# Converter.net
KiCad netlist of a schematic drawn in Altium Designer
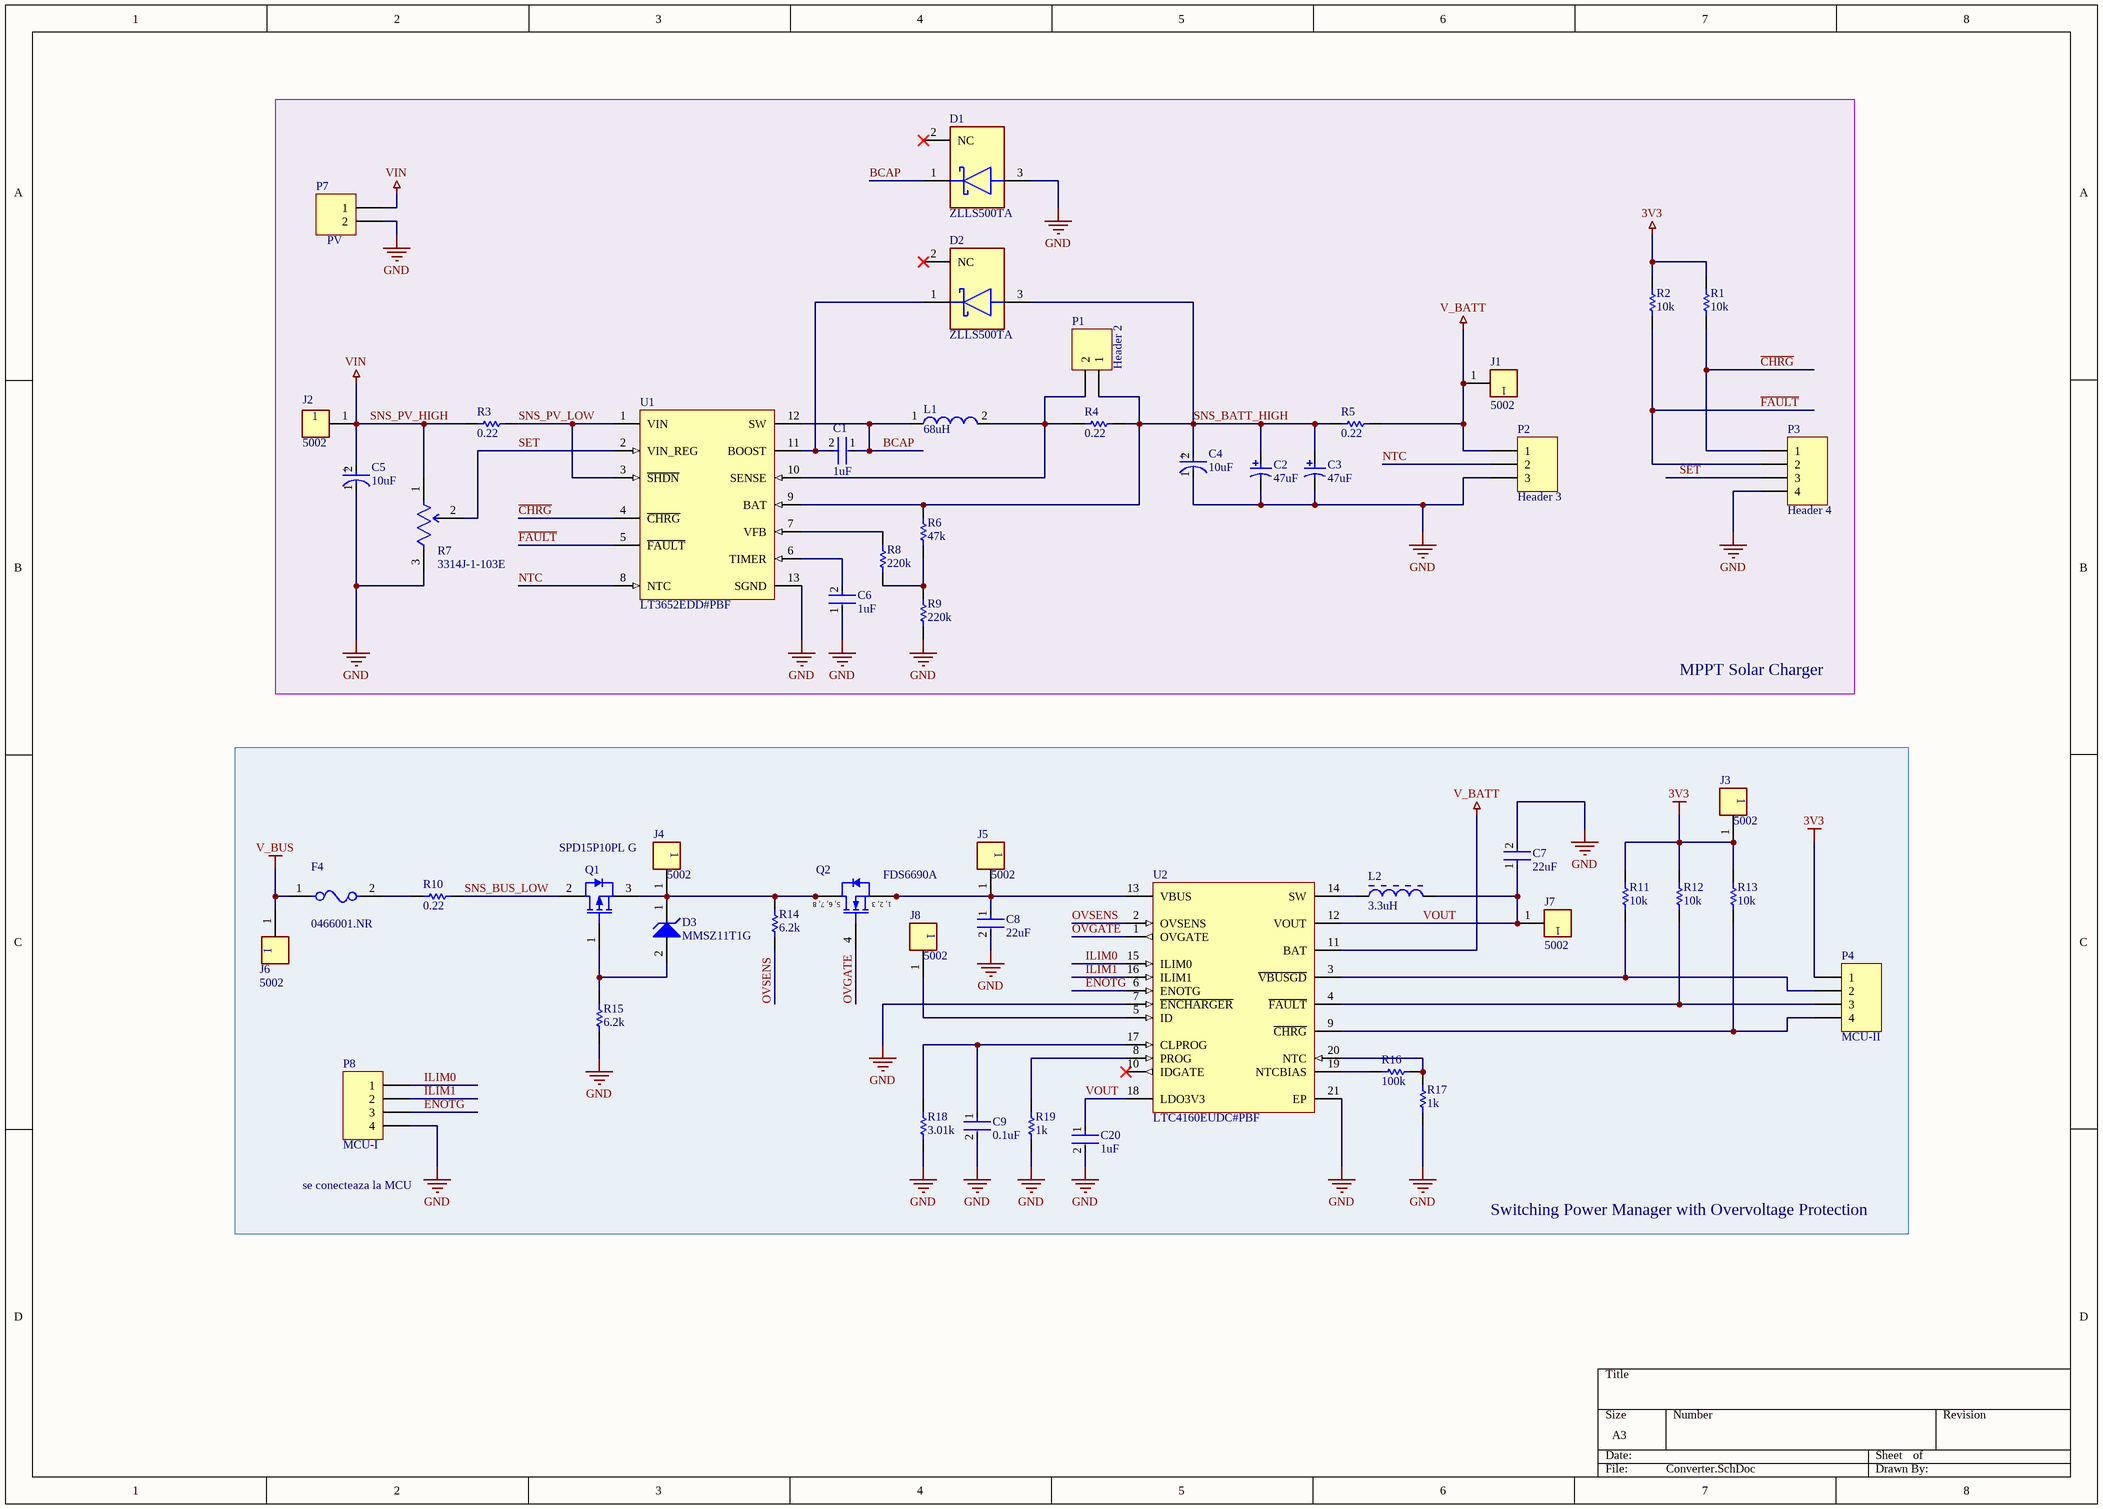
[diagram p0: Converter.SchDoc]

(export (version "E")
  (design (tool "Eeschema 10.0.6"))
  (components
    (comp (ref "C1")
      (value "1uF")
      (footprint "FP-C1608-080-0_1-IPC_B")
      (description "Multilayer Ceramic Capacitors 1μF ±10% 16V X7R SMD 0603")
      (fields (field (name "VOLTAGE") "16V") (field (name "TOLERANCE") "10%"))
      (libsource (lib "Altium Content Vault") (part "236180d848d6139a670b325ea6854c9"))
    )
    (comp (ref "C2")
      (value "47uF")
      (footprint "KEMT-T491-D_L")
      (fields (field (name "TOLERANCE") "10%"))
      (libsource (lib "Altium Content Vault") (part "CAP-P-2"))
    )
    (comp (ref "C3")
      (value "47uF")
      (footprint "KEMT-T491-D_L")
      (fields (field (name "TOLERANCE") "10%"))
      (libsource (lib "Altium Content Vault") (part "CAP-P-2"))
    )
    (comp (ref "C4")
      (value "10uF")
      (footprint "FP-T491C106K016AT-MFG")
      (description "CAP TANT 10UF 10% 16V 2312")
      (fields (field (name "VOLTAGE") "16V") (field (name "TOLERANCE") "10%"))
      (libsource (lib "Altium Content Vault") (part "a00bbbee19879c290e62620ae7e47b1"))
    )
    (comp (ref "C5")
      (value "10uF")
      (footprint "FP-T491D-MFG")
      (description "CAP TANT 10UF 10% 25V 2917")
      (fields (field (name "VOLTAGE") "25V") (field (name "TOLERANCE") "20%"))
      (libsource (lib "Altium Content Vault") (part "cf48714ba7e38822c1575c7ec0b6d1f"))
    )
    (comp (ref "C6")
      (value "1uF")
      (footprint "FP-C1608-080-0_1-IPC_B")
      (description "Multilayer Ceramic Capacitors 1μF ±10% 16V X7R SMD 0603")
      (fields (field (name "VOLTAGE") "16V") (field (name "TOLERANCE") "10%"))
      (libsource (lib "Altium Content Vault") (part "236180d848d6139a670b325ea6854c9"))
    )
    (comp (ref "C7")
      (value "22uF")
      (footprint "FP-C2012-125-0_2-IPC_C")
      (description "Multilayer Ceramic Capacitors 22μF ±10% 16V X5R SMD 0805")
      (fields (field (name "TOLERANCE") "10%") (field (name "VOLTAGE") "16V"))
      (libsource (lib "Altium Content Vault") (part "b4654b650e69147ec39a6b967a45e02"))
    )
    (comp (ref "C8")
      (value "22uF")
      (footprint "FP-C2012-125-0_2-IPC_C")
      (description "Multilayer Ceramic Capacitors 22μF ±10% 16V X5R SMD 0805")
      (fields (field (name "TOLERANCE") "10%") (field (name "VOLTAGE") "16V"))
      (libsource (lib "Altium Content Vault") (part "b4654b650e69147ec39a6b967a45e02"))
    )
    (comp (ref "C9")
      (value "0.1uF")
      (footprint "FP-GRM155-0_05-MFG")
      (description "CAP CER 0.1UF 16V X7R 0402")
      (fields (field (name "TOLERANCE") "5%") (field (name "VOLTAGE") "16V"))
      (libsource (lib "Altium Content Vault") (part "02cd4be3c70576c341d710602a673aa"))
    )
    (comp (ref "C20")
      (value "1uF")
      (footprint "FP-0603-L_1_6_0_15-W_0_81-IPC_A")
      (description "General Purpose Ceramic Capacitor, 0603, 1uF, 10%, X5R, 15%, 10V")
      (fields (field (name "TOLERANCE") "10%") (field (name "VOLTAGE") "10V"))
      (libsource (lib "Altium Content Vault") (part "02cd4be3c70576c341d710602a673aa"))
    )
    (comp (ref "D1")
      (value "ZLLS500TA")
      (footprint "FP-SOT23-IPC_B")
      (description "DIODE SCHOTTKY 40V 700MA SOT23-3")
      (libsource (lib "Altium Content Vault") (part "b02bf5cfd78647b0d44792585de17e4"))
    )
    (comp (ref "D2")
      (value "ZLLS500TA")
      (footprint "FP-SOT23-IPC_B")
      (description "DIODE SCHOTTKY 40V 700MA SOT23-3")
      (libsource (lib "Altium Content Vault") (part "b02bf5cfd78647b0d44792585de17e4"))
    )
    (comp (ref "D3")
      (value "MMSZ11T1G")
      (footprint "ONSC-SOD-123-2-425-04_V")
      (description "Zener Voltage Regulator, 500 mW, 2-Pin SOD-123, Pb-Free, Tape and Reel")
      (fields (field (name "MANUFACTURER") "On Semiconductor"))
      (libsource (lib "Altium Content Vault") (part "ONSC-K1A2-2"))
    )
    (comp (ref "F4")
      (value "0466001.NR")
      (footprint "FP-0466-MFG")
      (description "FUSE BOARD MNT 1A 63VAC/VDC 1206")
      (fields
        (field (name "MANUFACTURER") "Littelfuse Inc")
        (field (name "OCTOPART") "https://octopart.com/0466001.nr-littelfuse-566005")
      )
      (libsource (lib "Altium Content Vault") (part "5bcf9b9f640e542cf0359d10258e979"))
    )
    (comp (ref "J1")
      (value "5002")
      (footprint "FP-5002-MFG")
      (description "PC TEST POINT MINIATURE WHITE")
      (libsource (lib "") (part "1e4615820a309e3ce90f9e6d957b7fa_2"))
    )
    (comp (ref "J2")
      (value "5002")
      (footprint "FP-5002-MFG")
      (description "PC TEST POINT MINIATURE WHITE")
      (libsource (lib "") (part "1e4615820a309e3ce90f9e6d957b7fa_3"))
    )
    (comp (ref "J3")
      (value "5002")
      (footprint "FP-5002-MFG")
      (description "PC TEST POINT MINIATURE WHITE")
      (libsource (lib "Altium Content Vault") (part "1e4615820a309e3ce90f9e6d957b7fa"))
    )
    (comp (ref "J4")
      (value "5002")
      (footprint "FP-5002-MFG")
      (description "PC TEST POINT MINIATURE WHITE")
      (libsource (lib "Altium Content Vault") (part "1e4615820a309e3ce90f9e6d957b7fa"))
    )
    (comp (ref "J5")
      (value "5002")
      (footprint "FP-5002-MFG")
      (description "PC TEST POINT MINIATURE WHITE")
      (libsource (lib "Altium Content Vault") (part "1e4615820a309e3ce90f9e6d957b7fa"))
    )
    (comp (ref "J6")
      (value "5002")
      (footprint "FP-5002-MFG")
      (description "PC TEST POINT MINIATURE WHITE")
      (libsource (lib "") (part "1e4615820a309e3ce90f9e6d957b7fa_1"))
    )
    (comp (ref "J7")
      (value "5002")
      (footprint "FP-5002-MFG")
      (description "PC TEST POINT MINIATURE WHITE")
      (libsource (lib "") (part "1e4615820a309e3ce90f9e6d957b7fa_2"))
    )
    (comp (ref "J8")
      (value "5002")
      (footprint "FP-5002-MFG")
      (description "PC TEST POINT MINIATURE WHITE")
      (libsource (lib "Altium Content Vault") (part "1e4615820a309e3ce90f9e6d957b7fa"))
    )
    (comp (ref "L1")
      (value "68uH")
      (footprint "WE-PD2-XL")
      (description "SMD Power Inductor WE-PD2, L = 68.0 µH")
      (libsource (lib "Altium Content Vault") (part "PAS-IND-INDUCTOR-2"))
    )
    (comp (ref "L2")
      (value "3.3uH")
      (footprint "BOUR-SRN3015-2_V")
      (fields (field (name "MANUFACTURER") "Bourns") (field (name "PARTNUMBER") "SRN3015-3R3M"))
      (libsource (lib "Altium Content Vault") (part "BOUR-IND-2A"))
    )
    (comp (ref "P1")
      (value "Header 2")
      (footprint "HDR1X2")
      (description "Header, 2-Pin")
      (fields (field (name "PUBLISHER") "Altium Limited"))
      (libsource (lib "") (part "Header 2_1"))
    )
    (comp (ref "P2")
      (value "Header 3")
      (footprint "HDR1X3")
      (description "Header, 3-Pin")
      (fields (field (name "PUBLISHER") "Altium Limited"))
      (libsource (lib "Miscellaneous Connectors") (part "Header 3"))
    )
    (comp (ref "P3")
      (value "Header 4")
      (footprint "HDR1X4")
      (description "Header, 4-Pin")
      (fields (field (name "PUBLISHER") "Altium Limited"))
      (libsource (lib "") (part "Header 4_1"))
    )
    (comp (ref "P4")
      (value "MCU-II")
      (footprint "HDR1X4")
      (description "Header, 4-Pin")
      (fields (field (name "PUBLISHER") "Altium Limited"))
      (libsource (lib "") (part "Header 4_1"))
    )
    (comp (ref "P7")
      (value "PV")
      (footprint "HDR1X2")
      (description "Header, 2-Pin")
      (fields (field (name "PUBLISHER") "Altium Limited"))
      (libsource (lib "Miscellaneous Connectors") (part "Header 2"))
    )
    (comp (ref "P8")
      (value "MCU-I")
      (footprint "HDR1X4")
      (description "Header, 4-Pin")
      (fields (field (name "PUBLISHER") "Altium Limited"))
      (libsource (lib "Miscellaneous Connectors") (part "Header 4"))
    )
    (comp (ref "Q1")
      (value "SPD15P10PL G")
      (footprint "INF-PG-TO252-3-1_N")
      (fields (field (name "MANUFACTURER") "Infineon"))
      (libsource (lib "Altium Content Vault") (part "INF-PEMOS-GDS-3"))
    )
    (comp (ref "Q2")
      (value "FDS6690A")
      (footprint "FAIR-SOIC-8_V")
      (fields (field (name "MANUFACTURER") "Fairchild Semiconductor"))
      (libsource (lib "Altium Content Vault") (part "NEMOS-SSSGDDDD-8"))
    )
    (comp (ref "R1")
      (value "10k")
      (footprint "RESC1609X55X30LL15T15")
      (description "Chip Resistor, 10 KOhm, +/- 1%, 0.1 W, -55 to 155 degC, 0603 (1608 Metric), RoHS, Tape and Reel")
      (fields (field (name "TOLERANCE") "1%") (field (name "MANUFACTURER") "Panasonic"))
      (libsource (lib "Altium Content Vault") (part "RES-2"))
    )
    (comp (ref "R2")
      (value "10k")
      (footprint "RESC1609X55X30LL15T15")
      (description "Chip Resistor, 10 KOhm, +/- 1%, 0.1 W, -55 to 155 degC, 0603 (1608 Metric), RoHS, Tape and Reel")
      (fields (field (name "TOLERANCE") "1%") (field (name "MANUFACTURER") "Panasonic"))
      (libsource (lib "Altium Content Vault") (part "RES-2"))
    )
    (comp (ref "R3")
      (value "0.22")
      (footprint "RESC3216X70X50LL05T20")
      (fields (field (name "MANUFACTURER") "Panasonic") (field (name "PART NUMBER") "ERJ-8RQFR22V"))
      (libsource (lib "Altium Content Vault") (part "RES"))
    )
    (comp (ref "R4")
      (value "0.22")
      (footprint "RESC3216X70X50LL05T20")
      (fields (field (name "MANUFACTURER") "Panasonic") (field (name "PART NUMBER") "ERJ-8RQFR22V"))
      (libsource (lib "Altium Content Vault") (part "RES"))
    )
    (comp (ref "R5")
      (value "0.22")
      (footprint "RESC3216X70X50LL05T20")
      (fields (field (name "MANUFACTURER") "Panasonic") (field (name "PART NUMBER") "ERJ-8RQFR22V"))
      (libsource (lib "Altium Content Vault") (part "RES"))
    )
    (comp (ref "R6")
      (value "47k")
      (footprint "RESC1608X55X30NL15T15")
      (description "Chip Resistor, 47 KOhm, +/- 1%, 0.1 W, -55 to 155 degC, 0603 (1608 Metric), RoHS, Tape and Reel")
      (libsource (lib "Altium Content Vault") (part "RES-2"))
    )
    (comp (ref "R7")
      (value "3314J-1-103E")
      (footprint "FP-3314J-1-MFG")
      (description "TRIMMER 10K OHM 0.25W J LEAD TOP")
      (libsource (lib "Altium Content Vault") (part "13357d81287629c2fd191d242cfa50c"))
    )
    (comp (ref "R8")
      (value "220k")
      (footprint "RESC1608X55X25ML10T15")
      (description "Chip Resistor, 220 KOhm, +/- 1%, 100 mW, -55 to 155 degC, 0603 (1608 Metric), RoHS, Tape and Reel")
      (libsource (lib "Altium Content Vault") (part "RES-2"))
    )
    (comp (ref "R9")
      (value "220k")
      (footprint "RESC1608X55X25ML10T15")
      (description "Chip Resistor, 220 KOhm, +/- 1%, 100 mW, -55 to 155 degC, 0603 (1608 Metric), RoHS, Tape and Reel")
      (libsource (lib "Altium Content Vault") (part "RES-2"))
    )
    (comp (ref "R10")
      (value "0.22")
      (footprint "RESC3216X70X50LL05T20")
      (fields (field (name "MANUFACTURER") "Panasonic") (field (name "PART NUMBER") "ERJ-8RQFR22V"))
      (libsource (lib "Altium Content Vault") (part "RES"))
    )
    (comp (ref "R11")
      (value "10k")
      (footprint "RESC1609X55X30LL15T15")
      (description "Chip Resistor, 10 KOhm, +/- 1%, 0.1 W, -55 to 155 degC, 0603 (1608 Metric), RoHS, Tape and Reel")
      (fields (field (name "TOLERANCE") "1%") (field (name "MANUFACTURER") "Panasonic"))
      (libsource (lib "Altium Content Vault") (part "RES-2"))
    )
    (comp (ref "R12")
      (value "10k")
      (footprint "RESC1609X55X30LL15T15")
      (description "Chip Resistor, 10 KOhm, +/- 1%, 0.1 W, -55 to 155 degC, 0603 (1608 Metric), RoHS, Tape and Reel")
      (fields (field (name "TOLERANCE") "1%") (field (name "MANUFACTURER") "Panasonic"))
      (libsource (lib "Altium Content Vault") (part "RES-2"))
    )
    (comp (ref "R13")
      (value "10k")
      (footprint "RESC1609X55X30LL15T15")
      (description "Chip Resistor, 10 KOhm, +/- 1%, 0.1 W, -55 to 155 degC, 0603 (1608 Metric), RoHS, Tape and Reel")
      (fields (field (name "TOLERANCE") "1%") (field (name "MANUFACTURER") "Panasonic"))
      (libsource (lib "Altium Content Vault") (part "RES-2"))
    )
    (comp (ref "R14")
      (value "6.2k")
      (footprint "RESC1609X50X30ML10T20")
      (fields (field (name "PART NUMBER") "CRCW06036K20FKEA") (field (name "MANUFACTURER") "Vishay Dale"))
      (libsource (lib "Altium Content Vault") (part "RES"))
    )
    (comp (ref "R15")
      (value "6.2k")
      (footprint "RESC1609X50X30ML10T20")
      (fields (field (name "PART NUMBER") "CRCW06036K20FKEA") (field (name "MANUFACTURER") "Vishay Dale"))
      (libsource (lib "Altium Content Vault") (part "RES"))
    )
    (comp (ref "R16")
      (value "100k")
      (footprint "RESC1608X55X30ML15T15")
      (fields (field (name "PART NUMBER") "ERJ-3EKF1003V") (field (name "MANUFACTURER") "Panasonic"))
      (libsource (lib "Altium Content Vault") (part "RES"))
    )
    (comp (ref "R17")
      (value "1k")
      (footprint "RESC1608X55X30LL15T15")
      (fields (field (name "PART NUMBER") "ERJ-3EKF1001V") (field (name "MANUFACTURER") "Panasonic"))
      (libsource (lib "Altium Content Vault") (part "RES"))
    )
    (comp (ref "R18")
      (value "3.01k")
      (footprint "RESC1608X55X30LL15T15")
      (fields (field (name "PART NUMBER") "ERJ-3EKF3011V") (field (name "MANUFACTURER") "Panasonic"))
      (libsource (lib "Altium Content Vault") (part "RES"))
    )
    (comp (ref "R19")
      (value "1k")
      (footprint "RESC1608X55X30LL15T15")
      (fields (field (name "PART NUMBER") "ERJ-3EKF1001V") (field (name "MANUFACTURER") "Panasonic"))
      (libsource (lib "Altium Content Vault") (part "RES"))
    )
    (comp (ref "U1")
      (value "LT3652EDD#PBF")
      (footprint "LT-DD-12_V")
      (description "Power Tracking 2 A Battery Charger for Solar Power, 12-pin SON (DD-12), -40 to 125 degC, Pb-Free")
      (fields (field (name "MANUFACTURER") "Linear Technology"))
      (libsource (lib "Altium Content Vault") (part "LT-LT3652XX-12"))
    )
    (comp (ref "U2")
      (value "LTC4160EUDC#PBF")
      (footprint "LT-UDC-20_N")
      (fields (field (name "MANUFACTURER") "Linear Technology"))
      (libsource (lib "Altium Content Vault") (part "LT-LTC4160-UDC-20"))
    )
  )
  (nets
    (net (code "1") (name "/BCAP") (class "Default")
      (node (ref "C1") (pin "1") (pinfunction "1_1") (pintype "passive"))
      (node (ref "D1") (pin "1") (pinfunction "C_1") (pintype "passive"))
      (node (ref "L1") (pin "1") (pinfunction "1_1") (pintype "passive"))
      (node (ref "U1") (pin "12") (pinfunction "SW_12") (pintype "power_in"))
    )
    (net (code "2") (name "/ENOTG") (class "Default")
      (node (ref "P8") (pin "3") (pinfunction "3_3") (pintype "passive"))
      (node (ref "U2") (pin "6") (pinfunction "ENOTG_6") (pintype "input"))
    )
    (net (code "3") (name "/ILIM0") (class "Default")
      (node (ref "P8") (pin "1") (pinfunction "1_1") (pintype "passive"))
      (node (ref "U2") (pin "15") (pinfunction "ILIM0_15") (pintype "input"))
    )
    (net (code "4") (name "/ILIM1") (class "Default")
      (node (ref "P8") (pin "2") (pinfunction "2_2") (pintype "passive"))
      (node (ref "U2") (pin "16") (pinfunction "ILIM1_16") (pintype "input"))
    )
    (net (code "5") (name "/NTC") (class "Default")
      (node (ref "P2") (pin "2") (pinfunction "2_2") (pintype "passive"))
      (node (ref "U1") (pin "8") (pinfunction "NTC_8") (pintype "input"))
    )
    (net (code "6") (name "/OVGATE") (class "Default")
      (node (ref "Q2") (pin "4") (pinfunction "G_4") (pintype "passive"))
      (node (ref "U2") (pin "1") (pinfunction "OVGATE_1") (pintype "output"))
    )
    (net (code "7") (name "/OVSENS") (class "Default")
      (node (ref "R14") (pin "1") (pinfunction "1_1") (pintype "passive"))
      (node (ref "U2") (pin "2") (pinfunction "OVSENS_2") (pintype "input"))
    )
    (net (code "8") (name "/SET") (class "Default")
      (node (ref "P3") (pin "3") (pinfunction "3_3") (pintype "passive"))
      (node (ref "R7") (pin "2") (pinfunction "WIPER_2") (pintype "passive"))
      (node (ref "U1") (pin "2") (pinfunction "VIN_REG_2") (pintype "input"))
    )
    (net (code "9") (name "/SNS_BATT_HIGH") (class "Default")
      (node (ref "C2") (pin "1") (pinfunction "1_1") (pintype "passive"))
      (node (ref "C3") (pin "1") (pinfunction "1_1") (pintype "passive"))
      (node (ref "C4") (pin "2") (pinfunction "A_2") (pintype "passive"))
      (node (ref "D2") (pin "3") (pinfunction "A_3") (pintype "passive"))
      (node (ref "P1") (pin "1") (pinfunction "1_1") (pintype "passive"))
      (node (ref "R4") (pin "2") (pinfunction "2_2") (pintype "passive"))
      (node (ref "R5") (pin "1") (pinfunction "1_1") (pintype "passive"))
      (node (ref "R6") (pin "2") (pinfunction "2_2") (pintype "passive"))
      (node (ref "U1") (pin "9") (pinfunction "BAT_9") (pintype "input"))
    )
    (net (code "10") (name "/SNS_BUS_LOW") (class "Default")
      (node (ref "Q1") (pin "2") (pinfunction "DRAIN_2") (pintype "passive"))
      (node (ref "R10") (pin "2") (pinfunction "2_2") (pintype "passive"))
    )
    (net (code "11") (name "/SNS_PV_LOW") (class "Default")
      (node (ref "R3") (pin "2") (pinfunction "2_2") (pintype "passive"))
      (node (ref "U1") (pin "1") (pinfunction "VIN_1") (pintype "power_in"))
      (node (ref "U1") (pin "3") (pinfunction "~{SHDN}_3") (pintype "input"))
    )
    (net (code "12") (name "/VOUT") (class "Default")
      (node (ref "C20") (pin "1") (pinfunction "1_1") (pintype "passive"))
      (node (ref "C7") (pin "1") (pinfunction "1_1") (pintype "passive"))
      (node (ref "J7") (pin "1") (pinfunction "1_1") (pintype "passive"))
      (node (ref "L2") (pin "2") (pinfunction "2_2") (pintype "passive"))
      (node (ref "U2") (pin "12") (pinfunction "VOUT_12") (pintype "power_in"))
      (node (ref "U2") (pin "18") (pinfunction "LDO3V3_18") (pintype "power_in"))
    )
    (net (code "13") (name "/~{CHRG}") (class "Default")
      (node (ref "P3") (pin "1") (pinfunction "1_1") (pintype "passive"))
      (node (ref "R1") (pin "2") (pinfunction "2_2") (pintype "passive"))
      (node (ref "U1") (pin "4") (pinfunction "~{CHRG}_4") (pintype "tri_state"))
    )
    (net (code "14") (name "/~{FAULT}") (class "Default")
      (node (ref "P3") (pin "2") (pinfunction "2_2") (pintype "passive"))
      (node (ref "R2") (pin "2") (pinfunction "2_2") (pintype "passive"))
      (node (ref "U1") (pin "5") (pinfunction "~{FAULT}_5") (pintype "tri_state"))
    )
    (net (code "15") (name "3V3") (class "Default")
      (node (ref "J3") (pin "1") (pinfunction "1_1") (pintype "passive"))
      (node (ref "P4") (pin "1") (pinfunction "1_1") (pintype "passive"))
      (node (ref "R1") (pin "1") (pinfunction "1_1") (pintype "passive"))
      (node (ref "R11") (pin "2") (pinfunction "2_2") (pintype "passive"))
      (node (ref "R12") (pin "2") (pinfunction "2_2") (pintype "passive"))
      (node (ref "R13") (pin "2") (pinfunction "2_2") (pintype "passive"))
      (node (ref "R2") (pin "1") (pinfunction "1_1") (pintype "passive"))
    )
    (net (code "16") (name "GND") (class "Default")
      (node (ref "C2") (pin "2") (pinfunction "2_2") (pintype "passive"))
      (node (ref "C20") (pin "2") (pinfunction "2_2") (pintype "passive"))
      (node (ref "C3") (pin "2") (pinfunction "2_2") (pintype "passive"))
      (node (ref "C4") (pin "1") (pinfunction "C_1") (pintype "passive"))
      (node (ref "C5") (pin "1") (pinfunction "C_1") (pintype "passive"))
      (node (ref "C6") (pin "1") (pinfunction "1_1") (pintype "passive"))
      (node (ref "C7") (pin "2") (pinfunction "2_2") (pintype "passive"))
      (node (ref "C8") (pin "2") (pinfunction "2_2") (pintype "passive"))
      (node (ref "C9") (pin "2") (pinfunction "2_2") (pintype "passive"))
      (node (ref "D1") (pin "3") (pinfunction "A_3") (pintype "passive"))
      (node (ref "P2") (pin "3") (pinfunction "3_3") (pintype "passive"))
      (node (ref "P3") (pin "4") (pinfunction "4_4") (pintype "passive"))
      (node (ref "P7") (pin "2") (pinfunction "2_2") (pintype "passive"))
      (node (ref "P8") (pin "4") (pinfunction "4_4") (pintype "passive"))
      (node (ref "R15") (pin "1") (pinfunction "1_1") (pintype "passive"))
      (node (ref "R17") (pin "1") (pinfunction "1_1") (pintype "passive"))
      (node (ref "R18") (pin "1") (pinfunction "1_1") (pintype "passive"))
      (node (ref "R19") (pin "1") (pinfunction "1_1") (pintype "passive"))
      (node (ref "R7") (pin "3") (pinfunction "CW_3") (pintype "passive"))
      (node (ref "R9") (pin "1") (pinfunction "1_1") (pintype "passive"))
      (node (ref "U1") (pin "13") (pinfunction "SGND_13") (pintype "power_in"))
      (node (ref "U2") (pin "21") (pinfunction "EP_21") (pintype "power_in"))
      (node (ref "U2") (pin "7") (pinfunction "~{ENCHARGER}_7") (pintype "input"))
    )
    (net (code "17") (name "Net-(D2-C)") (class "Default")
      (node (ref "C1") (pin "2") (pinfunction "2_2") (pintype "passive"))
      (node (ref "D2") (pin "1") (pinfunction "C_1") (pintype "passive"))
      (node (ref "U1") (pin "11") (pinfunction "BOOST_11") (pintype "power_in"))
    )
    (net (code "18") (name "Net-(D3-A)") (class "Default")
      (node (ref "D3") (pin "2") (pinfunction "A_2") (pintype "passive"))
      (node (ref "Q1") (pin "1") (pinfunction "GATE_1") (pintype "passive"))
      (node (ref "R15") (pin "2") (pinfunction "2_2") (pintype "passive"))
    )
    (net (code "19") (name "Net-(D3-K)") (class "Default")
      (node (ref "D3") (pin "1") (pinfunction "K_1") (pintype "passive"))
      (node (ref "J4") (pin "1") (pinfunction "1_1") (pintype "passive"))
      (node (ref "Q1") (pin "3") (pinfunction "SOURCE_3") (pintype "passive"))
      (node (ref "Q2") (pin "5") (pinfunction "D_5") (pintype "passive"))
      (node (ref "Q2") (pin "6") (pinfunction "D_6") (pintype "passive"))
      (node (ref "Q2") (pin "7") (pinfunction "D_7") (pintype "passive"))
      (node (ref "Q2") (pin "8") (pinfunction "D_8") (pintype "passive"))
      (node (ref "R14") (pin "2") (pinfunction "2_2") (pintype "passive"))
    )
    (net (code "20") (name "Net-(F4-Pad2)") (class "Default")
      (node (ref "F4") (pin "2") (pinfunction "2_2") (pintype "passive"))
      (node (ref "R10") (pin "1") (pinfunction "1_1") (pintype "passive"))
    )
    (net (code "21") (name "Net-(R6-Pad1)") (class "Default")
      (node (ref "R6") (pin "1") (pinfunction "1_1") (pintype "passive"))
      (node (ref "R8") (pin "1") (pinfunction "1_1") (pintype "passive"))
      (node (ref "R9") (pin "2") (pinfunction "2_2") (pintype "passive"))
    )
    (net (code "22") (name "Net-(U1-SENSE)") (class "Default")
      (node (ref "L1") (pin "2") (pinfunction "2_2") (pintype "passive"))
      (node (ref "P1") (pin "2") (pinfunction "2_2") (pintype "passive"))
      (node (ref "R4") (pin "1") (pinfunction "1_1") (pintype "passive"))
      (node (ref "U1") (pin "10") (pinfunction "SENSE_10") (pintype "input"))
    )
    (net (code "23") (name "Net-(U1-TIMER)") (class "Default")
      (node (ref "C6") (pin "2") (pinfunction "2_2") (pintype "passive"))
      (node (ref "U1") (pin "6") (pinfunction "TIMER_6") (pintype "input"))
    )
    (net (code "24") (name "Net-(U1-VFB)") (class "Default")
      (node (ref "R8") (pin "2") (pinfunction "2_2") (pintype "passive"))
      (node (ref "U1") (pin "7") (pinfunction "VFB_7") (pintype "input"))
    )
    (net (code "25") (name "Net-(U2-CLPROG)") (class "Default")
      (node (ref "C9") (pin "1") (pinfunction "1_1") (pintype "passive"))
      (node (ref "R18") (pin "2") (pinfunction "2_2") (pintype "passive"))
      (node (ref "U2") (pin "17") (pinfunction "CLPROG_17") (pintype "input"))
    )
    (net (code "26") (name "Net-(U2-ID)") (class "Default")
      (node (ref "J8") (pin "1") (pinfunction "1_1") (pintype "passive"))
      (node (ref "U2") (pin "5") (pinfunction "ID_5") (pintype "input"))
    )
    (net (code "27") (name "Net-(U2-NTC)") (class "Default")
      (node (ref "R16") (pin "2") (pinfunction "2_2") (pintype "passive"))
      (node (ref "R17") (pin "2") (pinfunction "2_2") (pintype "passive"))
      (node (ref "U2") (pin "20") (pinfunction "NTC_20") (pintype "input"))
    )
    (net (code "28") (name "Net-(U2-NTCBIAS)") (class "Default")
      (node (ref "R16") (pin "1") (pinfunction "1_1") (pintype "passive"))
      (node (ref "U2") (pin "19") (pinfunction "NTCBIAS_19") (pintype "passive"))
    )
    (net (code "29") (name "Net-(U2-PROG)") (class "Default")
      (node (ref "R19") (pin "2") (pinfunction "2_2") (pintype "passive"))
      (node (ref "U2") (pin "8") (pinfunction "PROG_8") (pintype "input"))
    )
    (net (code "30") (name "Net-(U2-SW)") (class "Default")
      (node (ref "L2") (pin "1") (pinfunction "1_1") (pintype "passive"))
      (node (ref "U2") (pin "14") (pinfunction "SW_14") (pintype "power_in"))
    )
    (net (code "31") (name "Net-(U2-VBUS)") (class "Default")
      (node (ref "C8") (pin "1") (pinfunction "1_1") (pintype "passive"))
      (node (ref "J5") (pin "1") (pinfunction "1_1") (pintype "passive"))
      (node (ref "Q2") (pin "1") (pinfunction "S_1") (pintype "passive"))
      (node (ref "Q2") (pin "2") (pinfunction "S_2") (pintype "passive"))
      (node (ref "Q2") (pin "3") (pinfunction "S_3") (pintype "passive"))
      (node (ref "U2") (pin "13") (pinfunction "VBUS_13") (pintype "power_in"))
    )
    (net (code "32") (name "Net-(U2-~{CHRG})") (class "Default")
      (node (ref "P4") (pin "4") (pinfunction "4_4") (pintype "passive"))
      (node (ref "R13") (pin "1") (pinfunction "1_1") (pintype "passive"))
      (node (ref "U2") (pin "9") (pinfunction "~{CHRG}_9") (pintype "open_collector"))
    )
    (net (code "33") (name "Net-(U2-~{FAULT})") (class "Default")
      (node (ref "P4") (pin "3") (pinfunction "3_3") (pintype "passive"))
      (node (ref "R12") (pin "1") (pinfunction "1_1") (pintype "passive"))
      (node (ref "U2") (pin "4") (pinfunction "~{FAULT}_4") (pintype "open_collector"))
    )
    (net (code "34") (name "Net-(U2-~{VBUSGD})") (class "Default")
      (node (ref "P4") (pin "2") (pinfunction "2_2") (pintype "passive"))
      (node (ref "R11") (pin "1") (pinfunction "1_1") (pintype "passive"))
      (node (ref "U2") (pin "3") (pinfunction "~{VBUSGD}_3") (pintype "open_collector"))
    )
    (net (code "35") (name "VIN") (class "Default")
      (node (ref "C5") (pin "2") (pinfunction "A_2") (pintype "passive"))
      (node (ref "J2") (pin "1") (pinfunction "1_1") (pintype "passive"))
      (node (ref "P7") (pin "1") (pinfunction "1_1") (pintype "passive"))
      (node (ref "R3") (pin "1") (pinfunction "1_1") (pintype "passive"))
      (node (ref "R7") (pin "1") (pinfunction "CCW_1") (pintype "passive"))
    )
    (net (code "36") (name "V_BATT") (class "Default")
      (node (ref "J1") (pin "1") (pinfunction "1_1") (pintype "passive"))
      (node (ref "P2") (pin "1") (pinfunction "1_1") (pintype "passive"))
      (node (ref "R5") (pin "2") (pinfunction "2_2") (pintype "passive"))
      (node (ref "U2") (pin "11") (pinfunction "BAT_11") (pintype "power_in"))
    )
    (net (code "37") (name "V_BUS") (class "Default")
      (node (ref "F4") (pin "1") (pinfunction "1_1") (pintype "passive"))
      (node (ref "J6") (pin "1") (pinfunction "1_1") (pintype "passive"))
    )
    (net (code "38") (name "unconnected-(D1-NC-Pad2)") (class "Default")
      (node (ref "D1") (pin "2") (pinfunction "NC_2") (pintype "passive+no_connect"))
    )
    (net (code "39") (name "unconnected-(D2-NC-Pad2)") (class "Default")
      (node (ref "D2") (pin "2") (pinfunction "NC_2") (pintype "passive+no_connect"))
    )
    (net (code "40") (name "unconnected-(U2-IDGATE-Pad10)") (class "Default")
      (node (ref "U2") (pin "10") (pinfunction "IDGATE_10") (pintype "output+no_connect"))
    )
  )
)
